# Mikrobus-Proto-22.net
KiCad netlist of a schematic drawn in EAGLE
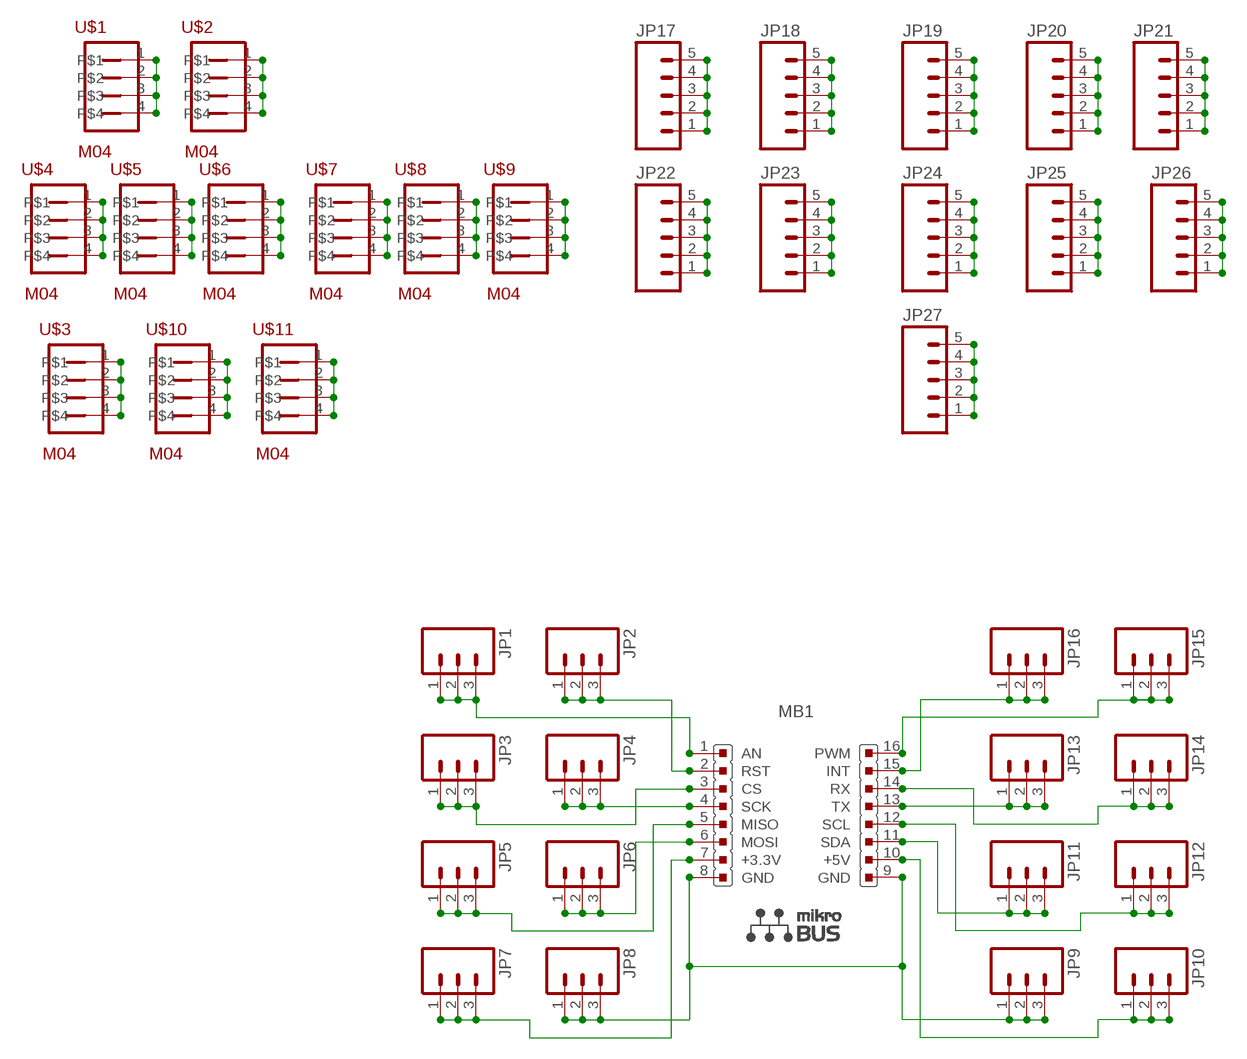
[diagram p0: schematic, sheet 1]

(export (version "E")
  (design (tool "Eeschema 10.0.6"))
  (components
    (comp (ref "JP1")
      (value "M03PTH")
      (footprint "eagle-import:1X03")
      (libsource (lib "eagle-import") (part "M03PTH"))
    )
    (comp (ref "JP2")
      (value "M03PTH")
      (footprint "eagle-import:1X03")
      (libsource (lib "eagle-import") (part "M03PTH"))
    )
    (comp (ref "JP3")
      (value "M03PTH")
      (footprint "eagle-import:1X03")
      (libsource (lib "eagle-import") (part "M03PTH"))
    )
    (comp (ref "JP4")
      (value "M03PTH")
      (footprint "eagle-import:1X03")
      (libsource (lib "eagle-import") (part "M03PTH"))
    )
    (comp (ref "JP5")
      (value "M03PTH")
      (footprint "eagle-import:1X03")
      (libsource (lib "eagle-import") (part "M03PTH"))
    )
    (comp (ref "JP6")
      (value "M03PTH")
      (footprint "eagle-import:1X03")
      (libsource (lib "eagle-import") (part "M03PTH"))
    )
    (comp (ref "JP7")
      (value "M03PTH")
      (footprint "eagle-import:1X03")
      (libsource (lib "eagle-import") (part "M03PTH"))
    )
    (comp (ref "JP8")
      (value "M03PTH")
      (footprint "eagle-import:1X03")
      (libsource (lib "eagle-import") (part "M03PTH"))
    )
    (comp (ref "JP9")
      (value "M03PTH")
      (footprint "eagle-import:1X03")
      (libsource (lib "eagle-import") (part "M03PTH"))
    )
    (comp (ref "JP10")
      (value "M03PTH")
      (footprint "eagle-import:1X03")
      (libsource (lib "eagle-import") (part "M03PTH"))
    )
    (comp (ref "JP11")
      (value "M03PTH")
      (footprint "eagle-import:1X03")
      (libsource (lib "eagle-import") (part "M03PTH"))
    )
    (comp (ref "JP12")
      (value "M03PTH")
      (footprint "eagle-import:1X03")
      (libsource (lib "eagle-import") (part "M03PTH"))
    )
    (comp (ref "JP13")
      (value "M03PTH")
      (footprint "eagle-import:1X03")
      (libsource (lib "eagle-import") (part "M03PTH"))
    )
    (comp (ref "JP14")
      (value "M03PTH")
      (footprint "eagle-import:1X03")
      (libsource (lib "eagle-import") (part "M03PTH"))
    )
    (comp (ref "JP15")
      (value "M03PTH")
      (footprint "eagle-import:1X03")
      (libsource (lib "eagle-import") (part "M03PTH"))
    )
    (comp (ref "JP16")
      (value "M03PTH")
      (footprint "eagle-import:1X03")
      (libsource (lib "eagle-import") (part "M03PTH"))
    )
    (comp (ref "JP17")
      (value "M05PTH")
      (footprint "eagle-import:1X05")
      (libsource (lib "eagle-import") (part "M05PTH"))
    )
    (comp (ref "JP18")
      (value "M05PTH")
      (footprint "eagle-import:1X05")
      (libsource (lib "eagle-import") (part "M05PTH"))
    )
    (comp (ref "JP19")
      (value "M05PTH")
      (footprint "eagle-import:1X05")
      (libsource (lib "eagle-import") (part "M05PTH"))
    )
    (comp (ref "JP20")
      (value "M05PTH")
      (footprint "eagle-import:1X05")
      (libsource (lib "eagle-import") (part "M05PTH"))
    )
    (comp (ref "JP21")
      (value "M05PTH")
      (footprint "eagle-import:1X05")
      (libsource (lib "eagle-import") (part "M05PTH"))
    )
    (comp (ref "JP22")
      (value "M05PTH")
      (footprint "eagle-import:1X05")
      (libsource (lib "eagle-import") (part "M05PTH"))
    )
    (comp (ref "JP23")
      (value "M05PTH")
      (footprint "eagle-import:1X05")
      (libsource (lib "eagle-import") (part "M05PTH"))
    )
    (comp (ref "JP24")
      (value "M05PTH")
      (footprint "eagle-import:1X05")
      (libsource (lib "eagle-import") (part "M05PTH"))
    )
    (comp (ref "JP25")
      (value "M05PTH")
      (footprint "eagle-import:1X05")
      (libsource (lib "eagle-import") (part "M05PTH"))
    )
    (comp (ref "JP26")
      (value "M05PTH")
      (footprint "eagle-import:1X05")
      (libsource (lib "eagle-import") (part "M05PTH"))
    )
    (comp (ref "JP27")
      (value "M05PTH")
      (footprint "eagle-import:1X05")
      (libsource (lib "eagle-import") (part "M05PTH"))
    )
    (comp (ref "MB1")
      (value "MIKROBUS")
      (footprint "eagle-import:MIKROBUS")
      (libsource (lib "eagle-import") (part "MIKROBUS"))
    )
    (comp (ref "U$1")
      (value "M04")
      (footprint "eagle-import:1X04")
      (libsource (lib "eagle-import") (part "M04"))
    )
    (comp (ref "U$2")
      (value "M04")
      (footprint "eagle-import:1X04")
      (libsource (lib "eagle-import") (part "M04"))
    )
    (comp (ref "U$3")
      (value "M04")
      (footprint "eagle-import:1X04")
      (libsource (lib "eagle-import") (part "M04"))
    )
    (comp (ref "U$4")
      (value "M04")
      (footprint "eagle-import:1X04")
      (libsource (lib "eagle-import") (part "M04"))
    )
    (comp (ref "U$5")
      (value "M04")
      (footprint "eagle-import:1X04")
      (libsource (lib "eagle-import") (part "M04"))
    )
    (comp (ref "U$6")
      (value "M04")
      (footprint "eagle-import:1X04")
      (libsource (lib "eagle-import") (part "M04"))
    )
    (comp (ref "U$7")
      (value "M04")
      (footprint "eagle-import:1X04")
      (libsource (lib "eagle-import") (part "M04"))
    )
    (comp (ref "U$8")
      (value "M04")
      (footprint "eagle-import:1X04")
      (libsource (lib "eagle-import") (part "M04"))
    )
    (comp (ref "U$9")
      (value "M04")
      (footprint "eagle-import:1X04")
      (libsource (lib "eagle-import") (part "M04"))
    )
    (comp (ref "U$10")
      (value "M04")
      (footprint "eagle-import:1X04")
      (libsource (lib "eagle-import") (part "M04"))
    )
    (comp (ref "U$11")
      (value "M04")
      (footprint "eagle-import:1X04")
      (libsource (lib "eagle-import") (part "M04"))
    )
  )
  (nets
    (net (code "1") (name "Net-(JP8-Pad1)") (class "Default")
      (node (ref "JP8") (pin "1") (pinfunction "1_1") (pintype "passive"))
      (node (ref "JP8") (pin "2") (pinfunction "2_2") (pintype "passive"))
      (node (ref "JP8") (pin "3") (pinfunction "3_3") (pintype "passive"))
      (node (ref "JP9") (pin "1") (pinfunction "1_1") (pintype "passive"))
      (node (ref "JP9") (pin "2") (pinfunction "2_2") (pintype "passive"))
      (node (ref "JP9") (pin "3") (pinfunction "3_3") (pintype "passive"))
      (node (ref "MB1") (pin "8") (pinfunction "GND_8") (pintype "passive"))
      (node (ref "MB1") (pin "9") (pinfunction "GND_9") (pintype "passive"))
    )
    (net (code "2") (name "Net-(JP17-Pad1)") (class "Default")
      (node (ref "JP17") (pin "1") (pinfunction "1_1") (pintype "passive"))
      (node (ref "JP17") (pin "2") (pinfunction "2_2") (pintype "passive"))
      (node (ref "JP17") (pin "3") (pinfunction "3_3") (pintype "passive"))
      (node (ref "JP17") (pin "4") (pinfunction "4_4") (pintype "passive"))
      (node (ref "JP17") (pin "5") (pinfunction "5_5") (pintype "passive"))
    )
    (net (code "3") (name "Net-(JP18-Pad1)") (class "Default")
      (node (ref "JP18") (pin "1") (pinfunction "1_1") (pintype "passive"))
      (node (ref "JP18") (pin "2") (pinfunction "2_2") (pintype "passive"))
      (node (ref "JP18") (pin "3") (pinfunction "3_3") (pintype "passive"))
      (node (ref "JP18") (pin "4") (pinfunction "4_4") (pintype "passive"))
      (node (ref "JP18") (pin "5") (pinfunction "5_5") (pintype "passive"))
    )
    (net (code "4") (name "Net-(JP19-Pad1)") (class "Default")
      (node (ref "JP19") (pin "1") (pinfunction "1_1") (pintype "passive"))
      (node (ref "JP19") (pin "2") (pinfunction "2_2") (pintype "passive"))
      (node (ref "JP19") (pin "3") (pinfunction "3_3") (pintype "passive"))
      (node (ref "JP19") (pin "4") (pinfunction "4_4") (pintype "passive"))
      (node (ref "JP19") (pin "5") (pinfunction "5_5") (pintype "passive"))
    )
    (net (code "5") (name "Net-(JP20-Pad1)") (class "Default")
      (node (ref "JP20") (pin "1") (pinfunction "1_1") (pintype "passive"))
      (node (ref "JP20") (pin "2") (pinfunction "2_2") (pintype "passive"))
      (node (ref "JP20") (pin "3") (pinfunction "3_3") (pintype "passive"))
      (node (ref "JP20") (pin "4") (pinfunction "4_4") (pintype "passive"))
      (node (ref "JP20") (pin "5") (pinfunction "5_5") (pintype "passive"))
    )
    (net (code "6") (name "Net-(JP21-Pad1)") (class "Default")
      (node (ref "JP21") (pin "1") (pinfunction "1_1") (pintype "passive"))
      (node (ref "JP21") (pin "2") (pinfunction "2_2") (pintype "passive"))
      (node (ref "JP21") (pin "3") (pinfunction "3_3") (pintype "passive"))
      (node (ref "JP21") (pin "4") (pinfunction "4_4") (pintype "passive"))
      (node (ref "JP21") (pin "5") (pinfunction "5_5") (pintype "passive"))
    )
    (net (code "7") (name "Net-(JP22-Pad1)") (class "Default")
      (node (ref "JP22") (pin "1") (pinfunction "1_1") (pintype "passive"))
      (node (ref "JP22") (pin "2") (pinfunction "2_2") (pintype "passive"))
      (node (ref "JP22") (pin "3") (pinfunction "3_3") (pintype "passive"))
      (node (ref "JP22") (pin "4") (pinfunction "4_4") (pintype "passive"))
      (node (ref "JP22") (pin "5") (pinfunction "5_5") (pintype "passive"))
    )
    (net (code "8") (name "Net-(JP23-Pad1)") (class "Default")
      (node (ref "JP23") (pin "1") (pinfunction "1_1") (pintype "passive"))
      (node (ref "JP23") (pin "2") (pinfunction "2_2") (pintype "passive"))
      (node (ref "JP23") (pin "3") (pinfunction "3_3") (pintype "passive"))
      (node (ref "JP23") (pin "4") (pinfunction "4_4") (pintype "passive"))
      (node (ref "JP23") (pin "5") (pinfunction "5_5") (pintype "passive"))
    )
    (net (code "9") (name "Net-(JP24-Pad1)") (class "Default")
      (node (ref "JP24") (pin "1") (pinfunction "1_1") (pintype "passive"))
      (node (ref "JP24") (pin "2") (pinfunction "2_2") (pintype "passive"))
      (node (ref "JP24") (pin "3") (pinfunction "3_3") (pintype "passive"))
      (node (ref "JP24") (pin "4") (pinfunction "4_4") (pintype "passive"))
      (node (ref "JP24") (pin "5") (pinfunction "5_5") (pintype "passive"))
    )
    (net (code "10") (name "Net-(JP25-Pad1)") (class "Default")
      (node (ref "JP25") (pin "1") (pinfunction "1_1") (pintype "passive"))
      (node (ref "JP25") (pin "2") (pinfunction "2_2") (pintype "passive"))
      (node (ref "JP25") (pin "3") (pinfunction "3_3") (pintype "passive"))
      (node (ref "JP25") (pin "4") (pinfunction "4_4") (pintype "passive"))
      (node (ref "JP25") (pin "5") (pinfunction "5_5") (pintype "passive"))
    )
    (net (code "11") (name "Net-(JP26-Pad1)") (class "Default")
      (node (ref "JP26") (pin "1") (pinfunction "1_1") (pintype "passive"))
      (node (ref "JP26") (pin "2") (pinfunction "2_2") (pintype "passive"))
      (node (ref "JP26") (pin "3") (pinfunction "3_3") (pintype "passive"))
      (node (ref "JP26") (pin "4") (pinfunction "4_4") (pintype "passive"))
      (node (ref "JP26") (pin "5") (pinfunction "5_5") (pintype "passive"))
    )
    (net (code "12") (name "Net-(JP27-Pad1)") (class "Default")
      (node (ref "JP27") (pin "1") (pinfunction "1_1") (pintype "passive"))
      (node (ref "JP27") (pin "2") (pinfunction "2_2") (pintype "passive"))
      (node (ref "JP27") (pin "3") (pinfunction "3_3") (pintype "passive"))
      (node (ref "JP27") (pin "4") (pinfunction "4_4") (pintype "passive"))
      (node (ref "JP27") (pin "5") (pinfunction "5_5") (pintype "passive"))
    )
    (net (code "13") (name "Net-(MB1-+3.3V)") (class "Default")
      (node (ref "JP7") (pin "1") (pinfunction "1_1") (pintype "passive"))
      (node (ref "JP7") (pin "2") (pinfunction "2_2") (pintype "passive"))
      (node (ref "JP7") (pin "3") (pinfunction "3_3") (pintype "passive"))
      (node (ref "MB1") (pin "7") (pinfunction "+3.3V_7") (pintype "passive"))
    )
    (net (code "14") (name "Net-(MB1-+5V)") (class "Default")
      (node (ref "JP10") (pin "1") (pinfunction "1_1") (pintype "passive"))
      (node (ref "JP10") (pin "2") (pinfunction "2_2") (pintype "passive"))
      (node (ref "JP10") (pin "3") (pinfunction "3_3") (pintype "passive"))
      (node (ref "MB1") (pin "10") (pinfunction "+5V_10") (pintype "passive"))
    )
    (net (code "15") (name "Net-(MB1-AN)") (class "Default")
      (node (ref "JP1") (pin "1") (pinfunction "1_1") (pintype "passive"))
      (node (ref "JP1") (pin "2") (pinfunction "2_2") (pintype "passive"))
      (node (ref "JP1") (pin "3") (pinfunction "3_3") (pintype "passive"))
      (node (ref "MB1") (pin "1") (pinfunction "AN_1") (pintype "bidirectional"))
    )
    (net (code "16") (name "Net-(MB1-CS)") (class "Default")
      (node (ref "JP3") (pin "1") (pinfunction "1_1") (pintype "passive"))
      (node (ref "JP3") (pin "2") (pinfunction "2_2") (pintype "passive"))
      (node (ref "JP3") (pin "3") (pinfunction "3_3") (pintype "passive"))
      (node (ref "MB1") (pin "3") (pinfunction "CS_3") (pintype "bidirectional"))
    )
    (net (code "17") (name "Net-(MB1-INT)") (class "Default")
      (node (ref "JP16") (pin "1") (pinfunction "1_1") (pintype "passive"))
      (node (ref "JP16") (pin "2") (pinfunction "2_2") (pintype "passive"))
      (node (ref "JP16") (pin "3") (pinfunction "3_3") (pintype "passive"))
      (node (ref "MB1") (pin "15") (pinfunction "INT_15") (pintype "bidirectional"))
    )
    (net (code "18") (name "Net-(MB1-MISO)") (class "Default")
      (node (ref "JP5") (pin "1") (pinfunction "1_1") (pintype "passive"))
      (node (ref "JP5") (pin "2") (pinfunction "2_2") (pintype "passive"))
      (node (ref "JP5") (pin "3") (pinfunction "3_3") (pintype "passive"))
      (node (ref "MB1") (pin "5") (pinfunction "MISO_5") (pintype "bidirectional"))
    )
    (net (code "19") (name "Net-(MB1-MOSI)") (class "Default")
      (node (ref "JP6") (pin "1") (pinfunction "1_1") (pintype "passive"))
      (node (ref "JP6") (pin "2") (pinfunction "2_2") (pintype "passive"))
      (node (ref "JP6") (pin "3") (pinfunction "3_3") (pintype "passive"))
      (node (ref "MB1") (pin "6") (pinfunction "MOSI_6") (pintype "bidirectional"))
    )
    (net (code "20") (name "Net-(MB1-PWM)") (class "Default")
      (node (ref "JP15") (pin "1") (pinfunction "1_1") (pintype "passive"))
      (node (ref "JP15") (pin "2") (pinfunction "2_2") (pintype "passive"))
      (node (ref "JP15") (pin "3") (pinfunction "3_3") (pintype "passive"))
      (node (ref "MB1") (pin "16") (pinfunction "PWM_16") (pintype "bidirectional"))
    )
    (net (code "21") (name "Net-(MB1-RST)") (class "Default")
      (node (ref "JP2") (pin "1") (pinfunction "1_1") (pintype "passive"))
      (node (ref "JP2") (pin "2") (pinfunction "2_2") (pintype "passive"))
      (node (ref "JP2") (pin "3") (pinfunction "3_3") (pintype "passive"))
      (node (ref "MB1") (pin "2") (pinfunction "RST_2") (pintype "bidirectional"))
    )
    (net (code "22") (name "Net-(MB1-RX)") (class "Default")
      (node (ref "JP14") (pin "1") (pinfunction "1_1") (pintype "passive"))
      (node (ref "JP14") (pin "2") (pinfunction "2_2") (pintype "passive"))
      (node (ref "JP14") (pin "3") (pinfunction "3_3") (pintype "passive"))
      (node (ref "MB1") (pin "14") (pinfunction "RX_14") (pintype "bidirectional"))
    )
    (net (code "23") (name "Net-(MB1-SCK)") (class "Default")
      (node (ref "JP4") (pin "1") (pinfunction "1_1") (pintype "passive"))
      (node (ref "JP4") (pin "2") (pinfunction "2_2") (pintype "passive"))
      (node (ref "JP4") (pin "3") (pinfunction "3_3") (pintype "passive"))
      (node (ref "MB1") (pin "4") (pinfunction "SCK_4") (pintype "bidirectional"))
    )
    (net (code "24") (name "Net-(MB1-SCL)") (class "Default")
      (node (ref "JP12") (pin "1") (pinfunction "1_1") (pintype "passive"))
      (node (ref "JP12") (pin "2") (pinfunction "2_2") (pintype "passive"))
      (node (ref "JP12") (pin "3") (pinfunction "3_3") (pintype "passive"))
      (node (ref "MB1") (pin "12") (pinfunction "SCL_12") (pintype "bidirectional"))
    )
    (net (code "25") (name "Net-(MB1-SDA)") (class "Default")
      (node (ref "JP11") (pin "1") (pinfunction "1_1") (pintype "passive"))
      (node (ref "JP11") (pin "2") (pinfunction "2_2") (pintype "passive"))
      (node (ref "JP11") (pin "3") (pinfunction "3_3") (pintype "passive"))
      (node (ref "MB1") (pin "11") (pinfunction "SDA_11") (pintype "bidirectional"))
    )
    (net (code "26") (name "Net-(MB1-TX)") (class "Default")
      (node (ref "JP13") (pin "1") (pinfunction "1_1") (pintype "passive"))
      (node (ref "JP13") (pin "2") (pinfunction "2_2") (pintype "passive"))
      (node (ref "JP13") (pin "3") (pinfunction "3_3") (pintype "passive"))
      (node (ref "MB1") (pin "13") (pinfunction "TX_13") (pintype "bidirectional"))
    )
    (net (code "27") (name "Net-(U$1-P$1)") (class "Default")
      (node (ref "U$1") (pin "1") (pinfunction "P$1_1") (pintype "passive"))
      (node (ref "U$1") (pin "2") (pinfunction "P$2_2") (pintype "passive"))
      (node (ref "U$1") (pin "3") (pinfunction "P$3_3") (pintype "passive"))
      (node (ref "U$1") (pin "4") (pinfunction "P$4_4") (pintype "passive"))
    )
    (net (code "28") (name "Net-(U$2-P$1)") (class "Default")
      (node (ref "U$2") (pin "1") (pinfunction "P$1_1") (pintype "passive"))
      (node (ref "U$2") (pin "2") (pinfunction "P$2_2") (pintype "passive"))
      (node (ref "U$2") (pin "3") (pinfunction "P$3_3") (pintype "passive"))
      (node (ref "U$2") (pin "4") (pinfunction "P$4_4") (pintype "passive"))
    )
    (net (code "29") (name "Net-(U$3-P$1)") (class "Default")
      (node (ref "U$3") (pin "1") (pinfunction "P$1_1") (pintype "passive"))
      (node (ref "U$3") (pin "2") (pinfunction "P$2_2") (pintype "passive"))
      (node (ref "U$3") (pin "3") (pinfunction "P$3_3") (pintype "passive"))
      (node (ref "U$3") (pin "4") (pinfunction "P$4_4") (pintype "passive"))
    )
    (net (code "30") (name "Net-(U$4-P$1)") (class "Default")
      (node (ref "U$4") (pin "1") (pinfunction "P$1_1") (pintype "passive"))
      (node (ref "U$4") (pin "2") (pinfunction "P$2_2") (pintype "passive"))
      (node (ref "U$4") (pin "3") (pinfunction "P$3_3") (pintype "passive"))
      (node (ref "U$4") (pin "4") (pinfunction "P$4_4") (pintype "passive"))
    )
    (net (code "31") (name "Net-(U$5-P$1)") (class "Default")
      (node (ref "U$5") (pin "1") (pinfunction "P$1_1") (pintype "passive"))
      (node (ref "U$5") (pin "2") (pinfunction "P$2_2") (pintype "passive"))
      (node (ref "U$5") (pin "3") (pinfunction "P$3_3") (pintype "passive"))
      (node (ref "U$5") (pin "4") (pinfunction "P$4_4") (pintype "passive"))
    )
    (net (code "32") (name "Net-(U$6-P$1)") (class "Default")
      (node (ref "U$6") (pin "1") (pinfunction "P$1_1") (pintype "passive"))
      (node (ref "U$6") (pin "2") (pinfunction "P$2_2") (pintype "passive"))
      (node (ref "U$6") (pin "3") (pinfunction "P$3_3") (pintype "passive"))
      (node (ref "U$6") (pin "4") (pinfunction "P$4_4") (pintype "passive"))
    )
    (net (code "33") (name "Net-(U$7-P$1)") (class "Default")
      (node (ref "U$7") (pin "1") (pinfunction "P$1_1") (pintype "passive"))
      (node (ref "U$7") (pin "2") (pinfunction "P$2_2") (pintype "passive"))
      (node (ref "U$7") (pin "3") (pinfunction "P$3_3") (pintype "passive"))
      (node (ref "U$7") (pin "4") (pinfunction "P$4_4") (pintype "passive"))
    )
    (net (code "34") (name "Net-(U$8-P$1)") (class "Default")
      (node (ref "U$8") (pin "1") (pinfunction "P$1_1") (pintype "passive"))
      (node (ref "U$8") (pin "2") (pinfunction "P$2_2") (pintype "passive"))
      (node (ref "U$8") (pin "3") (pinfunction "P$3_3") (pintype "passive"))
      (node (ref "U$8") (pin "4") (pinfunction "P$4_4") (pintype "passive"))
    )
    (net (code "35") (name "Net-(U$9-P$1)") (class "Default")
      (node (ref "U$9") (pin "1") (pinfunction "P$1_1") (pintype "passive"))
      (node (ref "U$9") (pin "2") (pinfunction "P$2_2") (pintype "passive"))
      (node (ref "U$9") (pin "3") (pinfunction "P$3_3") (pintype "passive"))
      (node (ref "U$9") (pin "4") (pinfunction "P$4_4") (pintype "passive"))
    )
    (net (code "36") (name "Net-(U$10-P$1)") (class "Default")
      (node (ref "U$10") (pin "1") (pinfunction "P$1_1") (pintype "passive"))
      (node (ref "U$10") (pin "2") (pinfunction "P$2_2") (pintype "passive"))
      (node (ref "U$10") (pin "3") (pinfunction "P$3_3") (pintype "passive"))
      (node (ref "U$10") (pin "4") (pinfunction "P$4_4") (pintype "passive"))
    )
    (net (code "37") (name "Net-(U$11-P$1)") (class "Default")
      (node (ref "U$11") (pin "1") (pinfunction "P$1_1") (pintype "passive"))
      (node (ref "U$11") (pin "2") (pinfunction "P$2_2") (pintype "passive"))
      (node (ref "U$11") (pin "3") (pinfunction "P$3_3") (pintype "passive"))
      (node (ref "U$11") (pin "4") (pinfunction "P$4_4") (pintype "passive"))
    )
  )
)
